# infinity.net
KiCad netlist of a schematic drawn in EAGLE
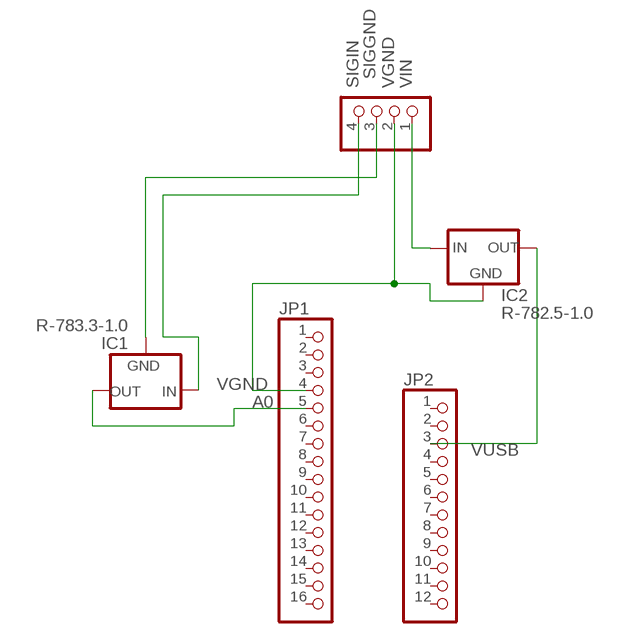
[diagram p0: schematic, sheet 1]

(export (version "E")
  (design (tool "Eeschema 10.0.6"))
  (components
    (comp (ref "IC1")
      (value "R-783.3-1.0")
      (footprint "eagle-import:SIP3")
      (fields (field (name "MF") "Recom"))
      (libsource (lib "eagle-import") (part "R-78-1.03.3"))
    )
    (comp (ref "IC2")
      (value "R-782.5-1.0")
      (footprint "eagle-import:SIP3")
      (fields (field (name "MF") "Recom"))
      (libsource (lib "eagle-import") (part "R-78-1.02.5"))
    )
    (comp (ref "JP1")
      (value "PINHD-1X16")
      (footprint "eagle-import:1X16")
      (libsource (lib "eagle-import") (part "PINHD-1X16"))
    )
    (comp (ref "JP2")
      (value "PINHD-1X12")
      (footprint "eagle-import:1X12")
      (libsource (lib "eagle-import") (part "PINHD-1X12"))
    )
    (comp (ref "SIGGND")
      (value "PINHD-1X4")
      (footprint "eagle-import:1X04")
      (libsource (lib "eagle-import") (part "PINHD-1X4"))
    )
  )
  (nets
    (net (code "1") (name "/A0") (class "Default")
      (node (ref "IC1") (pin "3") (pinfunction "OUT_3") (pintype "passive"))
      (node (ref "JP1") (pin "5") (pinfunction "5_5") (pintype "passive"))
    )
    (net (code "2") (name "/SIGIN") (class "Default")
      (node (ref "IC1") (pin "1") (pinfunction "IN_1") (pintype "input"))
      (node (ref "SIGGND") (pin "4") (pinfunction "4_4") (pintype "passive"))
    )
    (net (code "3") (name "/VGND") (class "Default")
      (node (ref "IC2") (pin "2") (pinfunction "GND_2") (pintype "input"))
      (node (ref "JP1") (pin "4") (pinfunction "4_4") (pintype "passive"))
      (node (ref "SIGGND") (pin "2") (pinfunction "2_2") (pintype "passive"))
    )
    (net (code "4") (name "/VIN") (class "Default")
      (node (ref "IC2") (pin "1") (pinfunction "IN_1") (pintype "input"))
      (node (ref "SIGGND") (pin "1") (pinfunction "1_1") (pintype "passive"))
    )
    (net (code "5") (name "/VUSB") (class "Default")
      (node (ref "IC2") (pin "3") (pinfunction "OUT_3") (pintype "passive"))
      (node (ref "JP2") (pin "3") (pinfunction "3_3") (pintype "passive"))
    )
    (net (code "6") (name "Net-(IC1-GND)") (class "Default")
      (node (ref "IC1") (pin "2") (pinfunction "GND_2") (pintype "input"))
      (node (ref "SIGGND") (pin "3") (pinfunction "3_3") (pintype "passive"))
    )
    (net (code "7") (name "unconnected-(JP1-Pad1)") (class "Default")
      (node (ref "JP1") (pin "1") (pinfunction "1_1") (pintype "passive"))
    )
    (net (code "8") (name "unconnected-(JP1-Pad2)") (class "Default")
      (node (ref "JP1") (pin "2") (pinfunction "2_2") (pintype "passive"))
    )
    (net (code "9") (name "unconnected-(JP1-Pad3)") (class "Default")
      (node (ref "JP1") (pin "3") (pinfunction "3_3") (pintype "passive"))
    )
    (net (code "10") (name "unconnected-(JP1-Pad6)") (class "Default")
      (node (ref "JP1") (pin "6") (pinfunction "6_6") (pintype "passive"))
    )
    (net (code "11") (name "unconnected-(JP1-Pad7)") (class "Default")
      (node (ref "JP1") (pin "7") (pinfunction "7_7") (pintype "passive"))
    )
    (net (code "12") (name "unconnected-(JP1-Pad8)") (class "Default")
      (node (ref "JP1") (pin "8") (pinfunction "8_8") (pintype "passive"))
    )
    (net (code "13") (name "unconnected-(JP1-Pad9)") (class "Default")
      (node (ref "JP1") (pin "9") (pinfunction "9_9") (pintype "passive"))
    )
    (net (code "14") (name "unconnected-(JP1-Pad10)") (class "Default")
      (node (ref "JP1") (pin "10") (pinfunction "10_10") (pintype "passive"))
    )
    (net (code "15") (name "unconnected-(JP1-Pad11)") (class "Default")
      (node (ref "JP1") (pin "11") (pinfunction "11_11") (pintype "passive"))
    )
    (net (code "16") (name "unconnected-(JP1-Pad12)") (class "Default")
      (node (ref "JP1") (pin "12") (pinfunction "12_12") (pintype "passive"))
    )
    (net (code "17") (name "unconnected-(JP1-Pad13)") (class "Default")
      (node (ref "JP1") (pin "13") (pinfunction "13_13") (pintype "passive"))
    )
    (net (code "18") (name "unconnected-(JP1-Pad14)") (class "Default")
      (node (ref "JP1") (pin "14") (pinfunction "14_14") (pintype "passive"))
    )
    (net (code "19") (name "unconnected-(JP1-Pad15)") (class "Default")
      (node (ref "JP1") (pin "15") (pinfunction "15_15") (pintype "passive"))
    )
    (net (code "20") (name "unconnected-(JP1-Pad16)") (class "Default")
      (node (ref "JP1") (pin "16") (pinfunction "16_16") (pintype "passive"))
    )
    (net (code "21") (name "unconnected-(JP2-Pad1)") (class "Default")
      (node (ref "JP2") (pin "1") (pinfunction "1_1") (pintype "passive"))
    )
    (net (code "22") (name "unconnected-(JP2-Pad2)") (class "Default")
      (node (ref "JP2") (pin "2") (pinfunction "2_2") (pintype "passive"))
    )
    (net (code "23") (name "unconnected-(JP2-Pad4)") (class "Default")
      (node (ref "JP2") (pin "4") (pinfunction "4_4") (pintype "passive"))
    )
    (net (code "24") (name "unconnected-(JP2-Pad5)") (class "Default")
      (node (ref "JP2") (pin "5") (pinfunction "5_5") (pintype "passive"))
    )
    (net (code "25") (name "unconnected-(JP2-Pad6)") (class "Default")
      (node (ref "JP2") (pin "6") (pinfunction "6_6") (pintype "passive"))
    )
    (net (code "26") (name "unconnected-(JP2-Pad7)") (class "Default")
      (node (ref "JP2") (pin "7") (pinfunction "7_7") (pintype "passive"))
    )
    (net (code "27") (name "unconnected-(JP2-Pad8)") (class "Default")
      (node (ref "JP2") (pin "8") (pinfunction "8_8") (pintype "passive"))
    )
    (net (code "28") (name "unconnected-(JP2-Pad9)") (class "Default")
      (node (ref "JP2") (pin "9") (pinfunction "9_9") (pintype "passive"))
    )
    (net (code "29") (name "unconnected-(JP2-Pad10)") (class "Default")
      (node (ref "JP2") (pin "10") (pinfunction "10_10") (pintype "passive"))
    )
    (net (code "30") (name "unconnected-(JP2-Pad11)") (class "Default")
      (node (ref "JP2") (pin "11") (pinfunction "11_11") (pintype "passive"))
    )
    (net (code "31") (name "unconnected-(JP2-Pad12)") (class "Default")
      (node (ref "JP2") (pin "12") (pinfunction "12_12") (pintype "passive"))
    )
  )
)
